# PCB_10_2_2020-06-05_09-00-42.net
KiCad netlist of a schematic drawn in EasyEDA
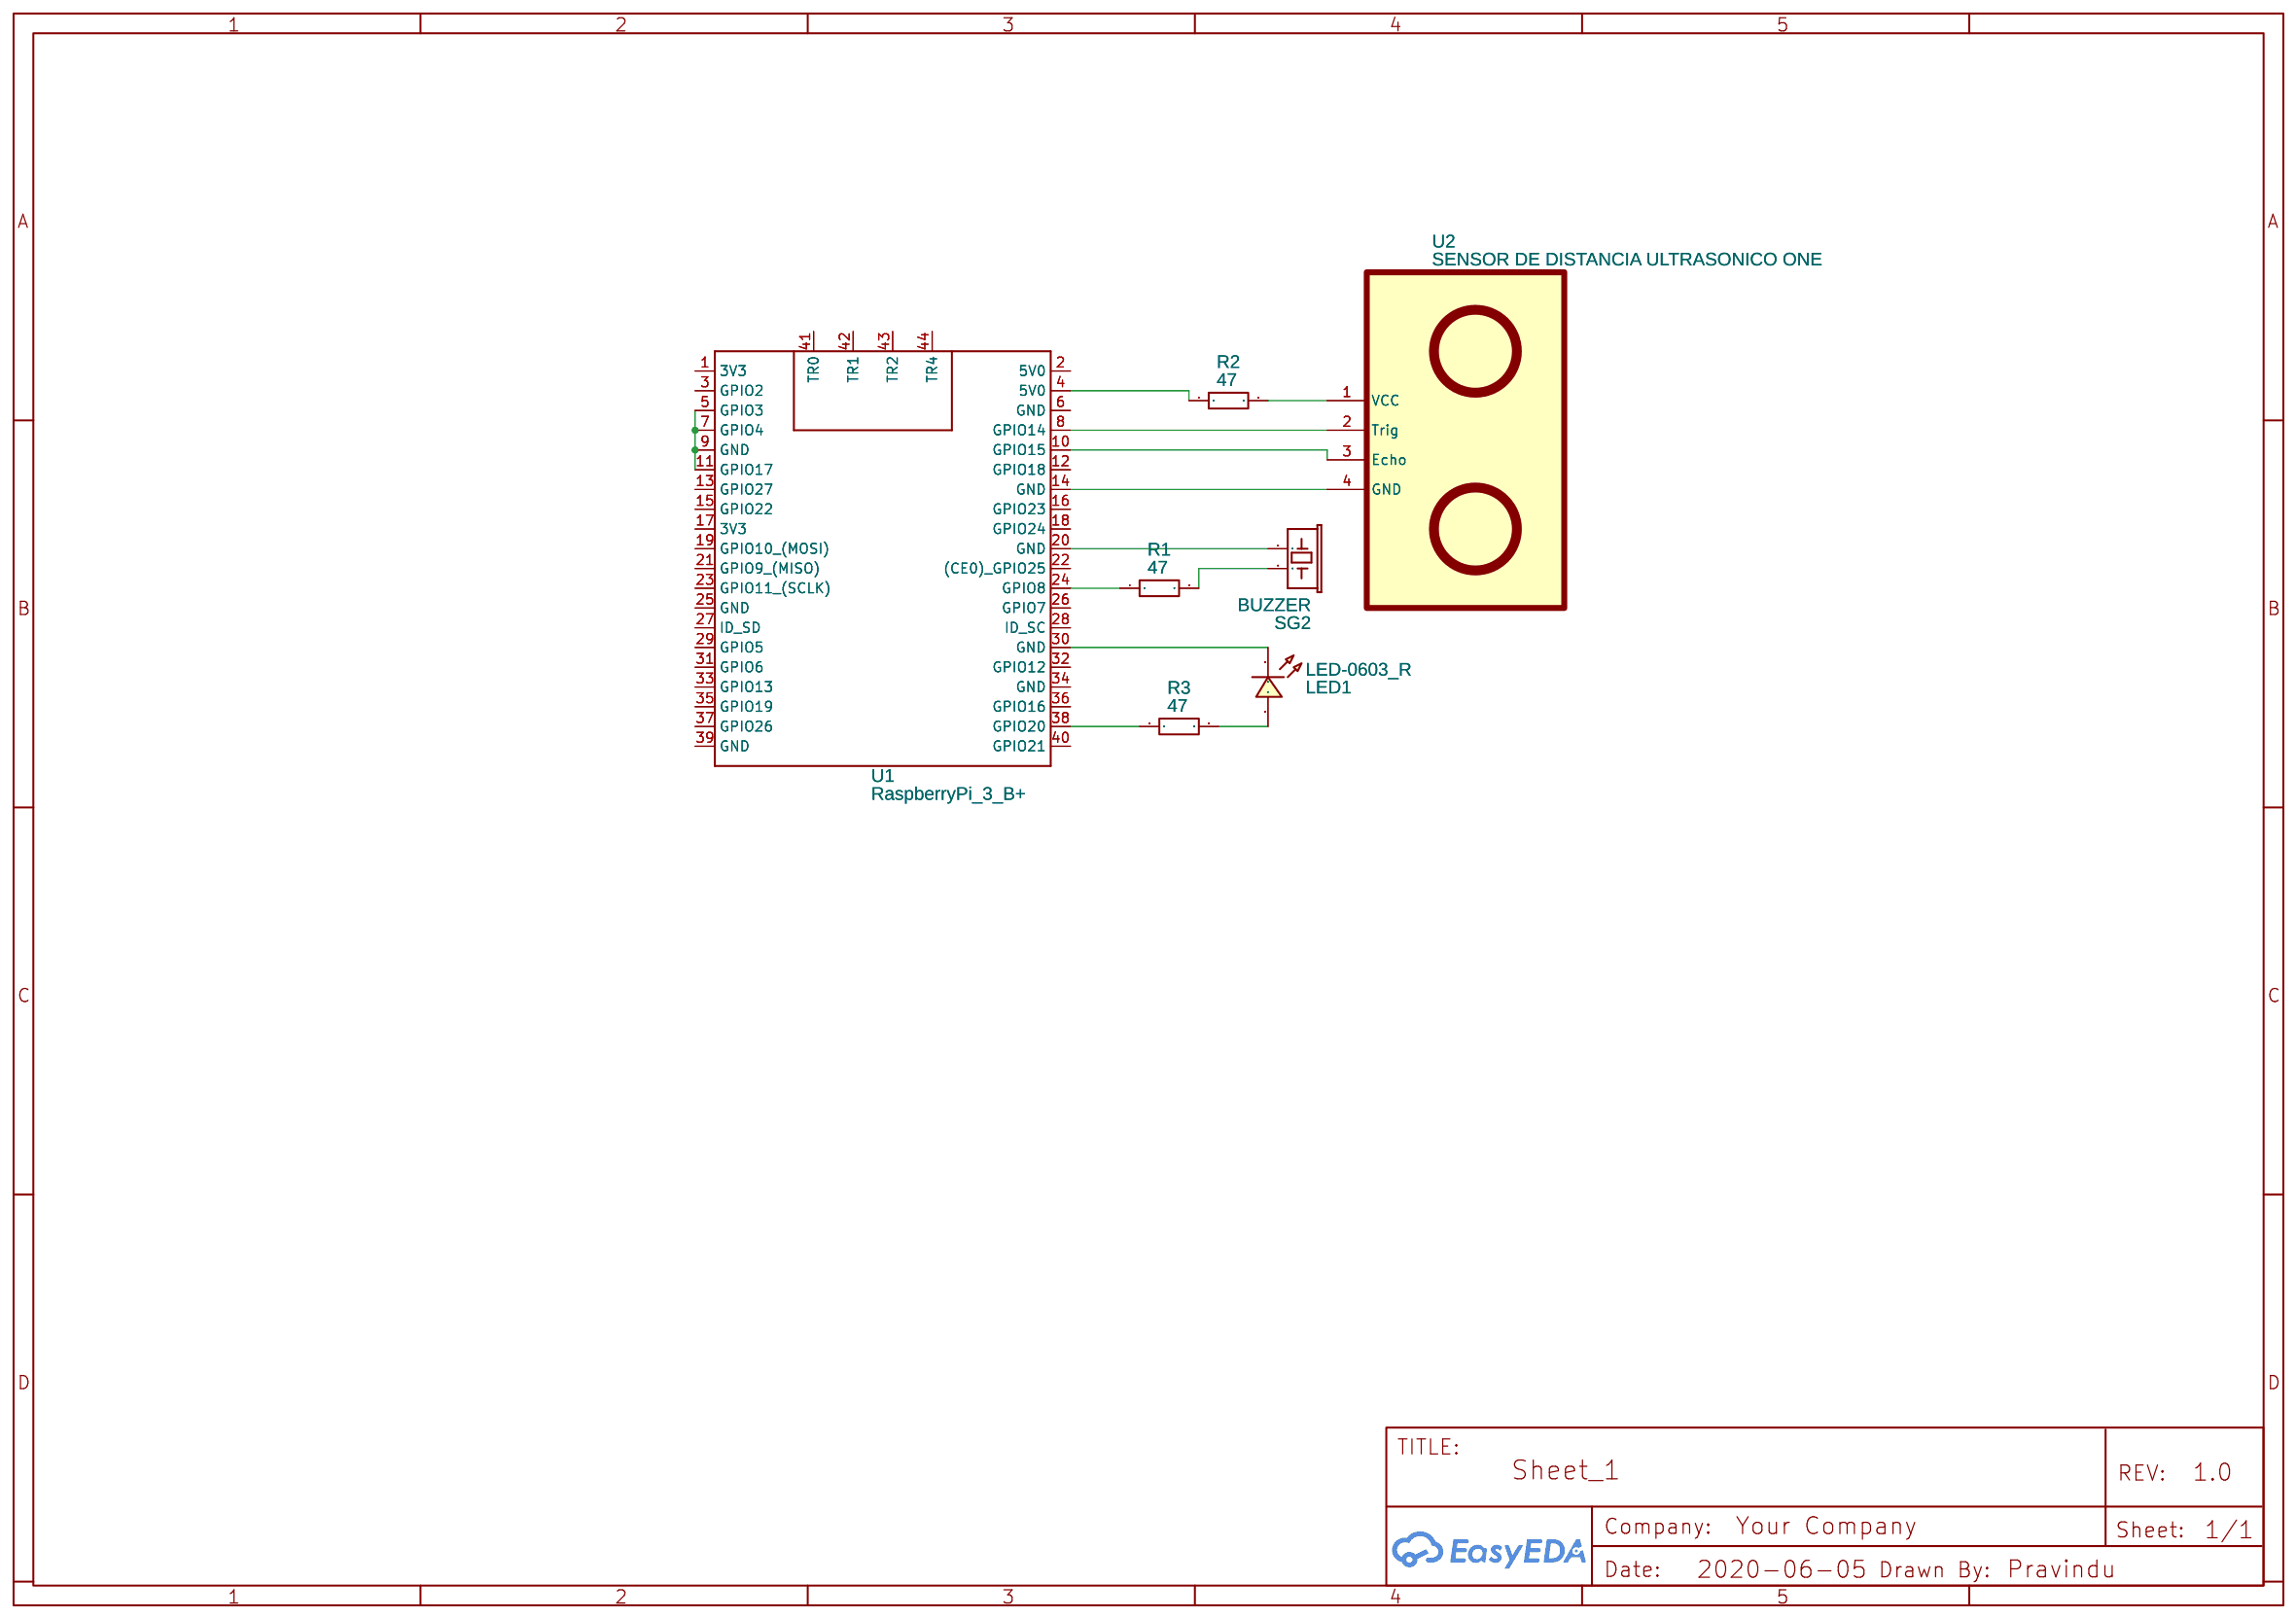
[diagram p0: schematic sheet]

(export (version "E")
  (design (tool "Eeschema 10.0.6"))
  (components
    (comp (ref "LED1")
      (value "LED-0603_R")
      (fields
        (field (name "BOM_Manufacturer Part") "19-217/R6C-AL1M2VY/3T")
        (field (name "BOM_Supplier Part") "C72044")
      )
      (libsource (lib "") (part "LED-0603_R"))
    )
    (comp (ref "R1")
      (value "47")
      (fields
        (field (name "BOM_Manufacturer Part") "KNP2W-47Ω±5% MK型")
        (field (name "BOM_Supplier Part") "C209824")
      )
      (libsource (lib "") (part "47Ω(470) ±5%"))
    )
    (comp (ref "R2")
      (value "47")
      (fields
        (field (name "BOM_Manufacturer Part") "KNP2W-47Ω±5% MK型")
        (field (name "BOM_Supplier Part") "C209824")
      )
      (libsource (lib "") (part "47Ω(470) ±5%"))
    )
    (comp (ref "R3")
      (value "47")
      (fields
        (field (name "BOM_Manufacturer Part") "KNP2W-47Ω±5% MK型")
        (field (name "BOM_Supplier Part") "C209824")
      )
      (libsource (lib "") (part "47Ω(470) ±5%"))
    )
    (comp (ref "SG2") (value "BUZZER") (libsource (lib "") (part "BUZZER")))
    (comp (ref "U1")
      (value "RaspberryPi_3_B+")
      (fields (field (name "BOM_Manufacturer Part") "RaspberryPi 3"))
      (libsource (lib "") (part "RaspberryPi_3_B+"))
    )
    (comp (ref "U2")
      (value "SENSOR DE DISTANCIA ULTRASONICO ONE")
      (libsource (lib "") (part "SENSOR DE DISTANCIA ULTRASONICO ONE"))
    )
  )
  (nets
    (net (code "1") (name "Net-(LED1-Pad1)") (class "Default")
      (node (ref "LED1") (pin "1") (pinfunction "1_1") (pintype "unspecified"))
      (node (ref "R3") (pin "2") (pinfunction "2_2") (pintype "unspecified"))
    )
    (net (code "2") (name "Net-(LED1-Pad2)") (class "Default")
      (node (ref "LED1") (pin "2") (pinfunction "2_2") (pintype "unspecified"))
      (node (ref "U1") (pin "30") (pinfunction "GND_30") (pintype "unspecified"))
    )
    (net (code "3") (name "Net-(R1-Pad2)") (class "Default")
      (node (ref "R1") (pin "2") (pinfunction "2_2") (pintype "unspecified"))
      (node (ref "SG2") (pin "2") (pinfunction "2_2") (pintype "unspecified"))
    )
    (net (code "4") (name "Net-(R2-Pad1)") (class "Default")
      (node (ref "R2") (pin "1") (pinfunction "1_1") (pintype "unspecified"))
      (node (ref "U1") (pin "4") (pinfunction "5V0_4") (pintype "unspecified"))
    )
    (net (code "5") (name "Net-(SG2-Pad1)") (class "Default")
      (node (ref "SG2") (pin "1") (pinfunction "1_1") (pintype "unspecified"))
      (node (ref "U1") (pin "20") (pinfunction "GND_20") (pintype "unspecified"))
    )
    (net (code "6") (name "Net-(U1-GPIO8)") (class "Default")
      (node (ref "R1") (pin "1") (pinfunction "1_1") (pintype "unspecified"))
      (node (ref "U1") (pin "24") (pinfunction "GPIO8_24") (pintype "unspecified"))
    )
    (net (code "7") (name "Net-(U1-GPIO14)") (class "Default")
      (node (ref "U1") (pin "8") (pinfunction "GPIO14_8") (pintype "unspecified"))
      (node (ref "U2") (pin "2") (pinfunction "Trig_2") (pintype "unspecified"))
    )
    (net (code "8") (name "Net-(U1-GPIO15)") (class "Default")
      (node (ref "U1") (pin "10") (pinfunction "GPIO15_10") (pintype "unspecified"))
      (node (ref "U2") (pin "3") (pinfunction "Echo_3") (pintype "unspecified"))
    )
    (net (code "9") (name "Net-(U1-GPIO17)") (class "Default")
      (node (ref "U1") (pin "11") (pinfunction "GPIO17_11") (pintype "unspecified"))
      (node (ref "U1") (pin "5") (pinfunction "GPIO3_5") (pintype "unspecified"))
      (node (ref "U1") (pin "7") (pinfunction "GPIO4_7") (pintype "unspecified"))
      (node (ref "U1") (pin "9") (pinfunction "GND_9") (pintype "unspecified"))
    )
    (net (code "10") (name "Net-(U1-GPIO20)") (class "Default")
      (node (ref "R3") (pin "1") (pinfunction "1_1") (pintype "unspecified"))
      (node (ref "U1") (pin "38") (pinfunction "GPIO20_38") (pintype "unspecified"))
    )
    (net (code "11") (name "Net-(U2-GND)") (class "Default")
      (node (ref "U1") (pin "14") (pinfunction "GND_14") (pintype "unspecified"))
      (node (ref "U2") (pin "4") (pinfunction "GND_4") (pintype "unspecified"))
    )
    (net (code "12") (name "Net-(U2-VCC)") (class "Default")
      (node (ref "R2") (pin "2") (pinfunction "2_2") (pintype "unspecified"))
      (node (ref "U2") (pin "1") (pinfunction "VCC_1") (pintype "unspecified"))
    )
    (net (code "13") (name "unconnected-(U1-(CE0)_GPIO25-Pad22)") (class "Default")
      (node (ref "U1") (pin "22") (pinfunction "(CE0)_GPIO25_22") (pintype "unspecified"))
    )
    (net (code "14") (name "unconnected-(U1-3V3-Pad1)") (class "Default")
      (node (ref "U1") (pin "1") (pinfunction "3V3_1") (pintype "unspecified"))
    )
    (net (code "15") (name "unconnected-(U1-3V3-Pad17)") (class "Default")
      (node (ref "U1") (pin "17") (pinfunction "3V3_17") (pintype "unspecified"))
    )
    (net (code "16") (name "unconnected-(U1-5V0-Pad2)") (class "Default")
      (node (ref "U1") (pin "2") (pinfunction "5V0_2") (pintype "unspecified"))
    )
    (net (code "17") (name "unconnected-(U1-GND-Pad6)") (class "Default")
      (node (ref "U1") (pin "6") (pinfunction "GND_6") (pintype "unspecified"))
    )
    (net (code "18") (name "unconnected-(U1-GND-Pad25)") (class "Default")
      (node (ref "U1") (pin "25") (pinfunction "GND_25") (pintype "unspecified"))
    )
    (net (code "19") (name "unconnected-(U1-GND-Pad34)") (class "Default")
      (node (ref "U1") (pin "34") (pinfunction "GND_34") (pintype "unspecified"))
    )
    (net (code "20") (name "unconnected-(U1-GND-Pad39)") (class "Default")
      (node (ref "U1") (pin "39") (pinfunction "GND_39") (pintype "unspecified"))
    )
    (net (code "21") (name "unconnected-(U1-GPIO2-Pad3)") (class "Default")
      (node (ref "U1") (pin "3") (pinfunction "GPIO2_3") (pintype "unspecified"))
    )
    (net (code "22") (name "unconnected-(U1-GPIO5-Pad29)") (class "Default")
      (node (ref "U1") (pin "29") (pinfunction "GPIO5_29") (pintype "unspecified"))
    )
    (net (code "23") (name "unconnected-(U1-GPIO6-Pad31)") (class "Default")
      (node (ref "U1") (pin "31") (pinfunction "GPIO6_31") (pintype "unspecified"))
    )
    (net (code "24") (name "unconnected-(U1-GPIO7-Pad26)") (class "Default")
      (node (ref "U1") (pin "26") (pinfunction "GPIO7_26") (pintype "unspecified"))
    )
    (net (code "25") (name "unconnected-(U1-GPIO9_(MISO)-Pad21)") (class "Default")
      (node (ref "U1") (pin "21") (pinfunction "GPIO9_(MISO)_21") (pintype "unspecified"))
    )
    (net (code "26") (name "unconnected-(U1-GPIO10_(MOSI)-Pad19)") (class "Default")
      (node (ref "U1") (pin "19") (pinfunction "GPIO10_(MOSI)_19") (pintype "unspecified"))
    )
    (net (code "27") (name "unconnected-(U1-GPIO11_(SCLK)-Pad23)") (class "Default")
      (node (ref "U1") (pin "23") (pinfunction "GPIO11_(SCLK)_23") (pintype "unspecified"))
    )
    (net (code "28") (name "unconnected-(U1-GPIO12-Pad32)") (class "Default")
      (node (ref "U1") (pin "32") (pinfunction "GPIO12_32") (pintype "unspecified"))
    )
    (net (code "29") (name "unconnected-(U1-GPIO13-Pad33)") (class "Default")
      (node (ref "U1") (pin "33") (pinfunction "GPIO13_33") (pintype "unspecified"))
    )
    (net (code "30") (name "unconnected-(U1-GPIO16-Pad36)") (class "Default")
      (node (ref "U1") (pin "36") (pinfunction "GPIO16_36") (pintype "unspecified"))
    )
    (net (code "31") (name "unconnected-(U1-GPIO18-Pad12)") (class "Default")
      (node (ref "U1") (pin "12") (pinfunction "GPIO18_12") (pintype "unspecified"))
    )
    (net (code "32") (name "unconnected-(U1-GPIO19-Pad35)") (class "Default")
      (node (ref "U1") (pin "35") (pinfunction "GPIO19_35") (pintype "unspecified"))
    )
    (net (code "33") (name "unconnected-(U1-GPIO21-Pad40)") (class "Default")
      (node (ref "U1") (pin "40") (pinfunction "GPIO21_40") (pintype "unspecified"))
    )
    (net (code "34") (name "unconnected-(U1-GPIO22-Pad15)") (class "Default")
      (node (ref "U1") (pin "15") (pinfunction "GPIO22_15") (pintype "unspecified"))
    )
    (net (code "35") (name "unconnected-(U1-GPIO23-Pad16)") (class "Default")
      (node (ref "U1") (pin "16") (pinfunction "GPIO23_16") (pintype "unspecified"))
    )
    (net (code "36") (name "unconnected-(U1-GPIO24-Pad18)") (class "Default")
      (node (ref "U1") (pin "18") (pinfunction "GPIO24_18") (pintype "unspecified"))
    )
    (net (code "37") (name "unconnected-(U1-GPIO26-Pad37)") (class "Default")
      (node (ref "U1") (pin "37") (pinfunction "GPIO26_37") (pintype "unspecified"))
    )
    (net (code "38") (name "unconnected-(U1-GPIO27-Pad13)") (class "Default")
      (node (ref "U1") (pin "13") (pinfunction "GPIO27_13") (pintype "unspecified"))
    )
    (net (code "39") (name "unconnected-(U1-ID_SC-Pad28)") (class "Default")
      (node (ref "U1") (pin "28") (pinfunction "ID_SC_28") (pintype "unspecified"))
    )
    (net (code "40") (name "unconnected-(U1-ID_SD-Pad27)") (class "Default")
      (node (ref "U1") (pin "27") (pinfunction "ID_SD_27") (pintype "unspecified"))
    )
    (net (code "41") (name "unconnected-(U1-TR0-Pad41)") (class "Default")
      (node (ref "U1") (pin "41") (pinfunction "TR0_41") (pintype "unspecified"))
    )
    (net (code "42") (name "unconnected-(U1-TR1-Pad42)") (class "Default")
      (node (ref "U1") (pin "42") (pinfunction "TR1_42") (pintype "unspecified"))
    )
    (net (code "43") (name "unconnected-(U1-TR2-Pad43)") (class "Default")
      (node (ref "U1") (pin "43") (pinfunction "TR2_43") (pintype "unspecified"))
    )
    (net (code "44") (name "unconnected-(U1-TR4-Pad44)") (class "Default")
      (node (ref "U1") (pin "44") (pinfunction "TR4_44") (pintype "unspecified"))
    )
  )
)
